# Digital.net
KiCad netlist of a schematic drawn in Altium Designer
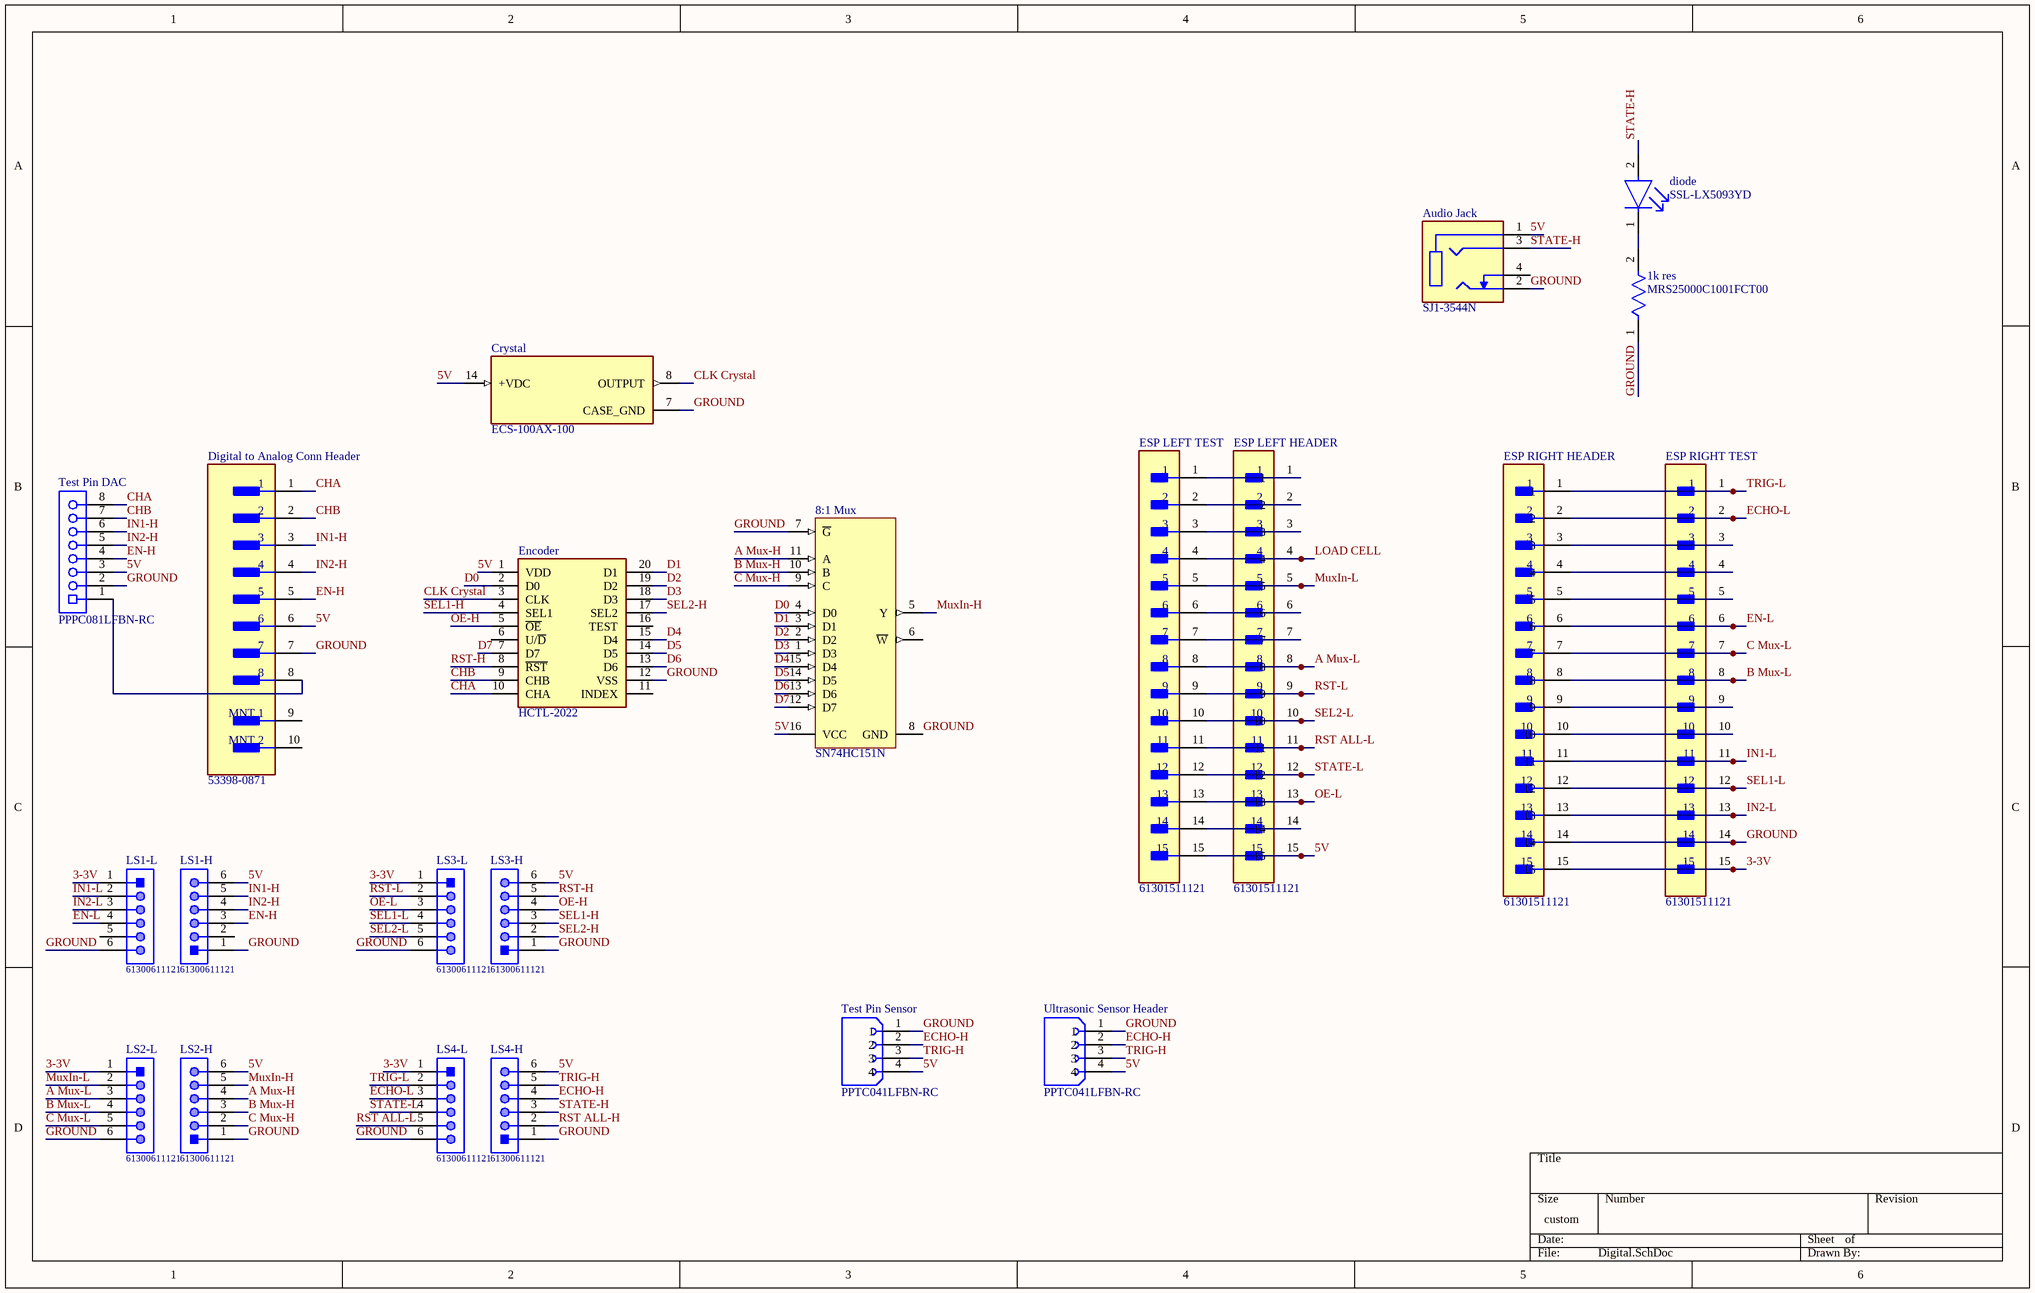
[diagram p0: Digital.SchDoc]

(export (version "E")
  (design (tool "Eeschema 10.0.6"))
  (components
    (comp (ref "1k res")
      (value "MRS25000C1001FCT00")
      (footprint "FP-MRS25-MFG")
      (description "RES 1K OHM 0.6W 1% AXIAL")
      (fields (field (name "TOLERANCE") "1%"))
      (libsource (lib "Altium Content Vault") (part "1029c3af85768c4190bb7ad29bc67b5"))
    )
    (comp (ref "8:1 Mux")
      (value "SN74HC151N")
      (footprint "N0016A")
      (description "8-Line To 1-Line Data Selectors/Multiplexers, N0016A, TUBE")
      (fields
        (field (name "GENERIC PART NUMBER") "SN74HC151")
        (field (name "MANUFACTURER") "Texas Instruments")
      )
      (libsource (lib "Altium Content Vault") (part "TI-SNX4XXX151-16"))
    )
    (comp (ref "Audio Jack")
      (value "SJ1-3544N")
      (footprint "CUI_SJ1-3544N")
      (description "3.5 mm Right-Angle Stereo Jack, 4 Pin PCB Mount, Non-Threaded")
      (libsource (lib "SJ1-3544N") (part "SJ1-3544N"))
    )
    (comp (ref "Crystal")
      (value "ECS-100AX-100")
      (footprint "OSC_ECS-100AX-100")
      (description "Oscillator  14-DIP, 4 Leads (Full Size, Metal Can)")
      (libsource (lib "ECS-100AX-100") (part "ECS-100AX-100"))
    )
    (comp (ref "Digital to Analog Conn Header")
      (value "53398-0871")
      (footprint "FP-53398-0871-MFG")
      (description "CONN HEADER SMD 8POS 1.25MM")
      (fields
        (field (name "MANUFACTURER") "Molex")
        (field (name "OCTOPART") "https://octopart.com/53398-0871-molex-655298")
      )
      (libsource (lib "Altium Content Vault") (part "98b5586d6b3804e276fbd0410cd4945"))
    )
    (comp (ref "diode")
      (value "SSL-LX5093YD")
      (footprint "FP-SSL-LX5093YD-MFG")
      (description "LED YELLOW DIFFUSED T-1 3/4 T/H")
      (libsource (lib "Altium Content Vault") (part "8706943c75ba83719d021d2fdc84c58"))
    )
    (comp (ref "Encoder")
      (value "HCTL-2022")
      (footprint "DIP762W56P254L2591H330Q20N")
      (description "HCTL-2022 quadrature decoder/counter ic Avago Technologies HCTL-2022 Decoder, 20-Pin PDIP")
      (fields (field (name "MOUSER PART NUMBER") "630-HCTL-2022"))
      (libsource (lib "HCTL-2022") (part "HCTL-2022"))
    )
    (comp (ref "ESP LEFT HEADER")
      (value "61301511121")
      (footprint "FP-61301511121-MFG")
      (description "CONN HEADER VERT 15POS 2.54MM")
      (libsource (lib "") (part "9e54aee09c46527fb07af492d4d8164_1"))
    )
    (comp (ref "ESP LEFT TEST")
      (value "61301511121")
      (footprint "FP-61301511121-MFG")
      (description "CONN HEADER VERT 15POS 2.54MM")
      (libsource (lib "Altium Content Vault") (part "9e54aee09c46527fb07af492d4d8164"))
    )
    (comp (ref "ESP RIGHT HEADER")
      (value "61301511121")
      (footprint "FP-61301511121-MFG")
      (description "CONN HEADER VERT 15POS 2.54MM")
      (libsource (lib "") (part "9e54aee09c46527fb07af492d4d8164_1"))
    )
    (comp (ref "ESP RIGHT TEST")
      (value "61301511121")
      (footprint "FP-61301511121-MFG")
      (description "CONN HEADER VERT 15POS 2.54MM")
      (libsource (lib "Altium Content Vault") (part "9e54aee09c46527fb07af492d4d8164"))
    )
    (comp (ref "LS1-H")
      (value "61300611121")
      (footprint "61300611121")
      (description "THT Vertical Pin Header WR-PHD, Pitch 2.54 mm, Single Row, 6 pins")
      (fields (field (name "MANUFACTURER") "Wurth Elektronik") (field (name "PUBLISHER") "WurthElektronik"))
      (libsource (lib "") (part "WE-CN-1P-M-R6_1"))
    )
    (comp (ref "LS1-L")
      (value "61300611121")
      (footprint "61300611121")
      (description "THT Vertical Pin Header WR-PHD, Pitch 2.54 mm, Single Row, 6 pins")
      (fields (field (name "MANUFACTURER") "Wurth Elektronik") (field (name "PUBLISHER") "WurthElektronik"))
      (libsource (lib "Altium Content Vault") (part "WE-CN-1P-M-R6"))
    )
    (comp (ref "LS2-H")
      (value "61300611121")
      (footprint "61300611121")
      (description "THT Vertical Pin Header WR-PHD, Pitch 2.54 mm, Single Row, 6 pins")
      (fields (field (name "MANUFACTURER") "Wurth Elektronik") (field (name "PUBLISHER") "WurthElektronik"))
      (libsource (lib "") (part "WE-CN-1P-M-R6_1"))
    )
    (comp (ref "LS2-L")
      (value "61300611121")
      (footprint "61300611121")
      (description "THT Vertical Pin Header WR-PHD, Pitch 2.54 mm, Single Row, 6 pins")
      (fields (field (name "MANUFACTURER") "Wurth Elektronik") (field (name "PUBLISHER") "WurthElektronik"))
      (libsource (lib "Altium Content Vault") (part "WE-CN-1P-M-R6"))
    )
    (comp (ref "LS3-H")
      (value "61300611121")
      (footprint "61300611121")
      (description "THT Vertical Pin Header WR-PHD, Pitch 2.54 mm, Single Row, 6 pins")
      (fields (field (name "MANUFACTURER") "Wurth Elektronik") (field (name "PUBLISHER") "WurthElektronik"))
      (libsource (lib "") (part "WE-CN-1P-M-R6_1"))
    )
    (comp (ref "LS3-L")
      (value "61300611121")
      (footprint "61300611121")
      (description "THT Vertical Pin Header WR-PHD, Pitch 2.54 mm, Single Row, 6 pins")
      (fields (field (name "MANUFACTURER") "Wurth Elektronik") (field (name "PUBLISHER") "WurthElektronik"))
      (libsource (lib "Altium Content Vault") (part "WE-CN-1P-M-R6"))
    )
    (comp (ref "LS4-H")
      (value "61300611121")
      (footprint "61300611121")
      (description "THT Vertical Pin Header WR-PHD, Pitch 2.54 mm, Single Row, 6 pins")
      (fields (field (name "MANUFACTURER") "Wurth Elektronik") (field (name "PUBLISHER") "WurthElektronik"))
      (libsource (lib "") (part "WE-CN-1P-M-R6_1"))
    )
    (comp (ref "LS4-L")
      (value "61300611121")
      (footprint "61300611121")
      (description "THT Vertical Pin Header WR-PHD, Pitch 2.54 mm, Single Row, 6 pins")
      (fields (field (name "MANUFACTURER") "Wurth Elektronik") (field (name "PUBLISHER") "WurthElektronik"))
      (libsource (lib "Altium Content Vault") (part "WE-CN-1P-M-R6"))
    )
    (comp (ref "Test Pin DAC")
      (value "PPPC081LFBN-RC")
      (footprint "SLIN-PPPC081LFBN-RC_V")
      (libsource (lib "Altium Content Vault") (part "CN-1P-F-R8"))
    )
    (comp (ref "Test Pin Sensor")
      (value "PPTC041LFBN-RC")
      (footprint "SULLINS_PPTC041LFBN-RC")
      (description "4 Position Header Connector 0.100 (2.54mm) Through Hole Tin")
      (fields (field (name "MF") "Sullins Connector") (field (name "DIGI-KEY_PART_NUMBER") "S7002-ND"))
      (libsource (lib "PPTC041LFBN-RC") (part "PPTC041LFBN-RC"))
    )
    (comp (ref "Ultrasonic Sensor Header")
      (value "PPTC041LFBN-RC")
      (footprint "SULLINS_PPTC041LFBN-RC")
      (description "4 Position Header Connector 0.100 (2.54mm) Through Hole Tin")
      (fields (field (name "MF") "Sullins Connector") (field (name "DIGI-KEY_PART_NUMBER") "S7002-ND"))
      (libsource (lib "PPTC041LFBN-RC") (part "PPTC041LFBN-RC"))
    )
  )
  (nets
    (net (code "1") (name "/3-3V") (class "Default")
      (node (ref "ESP RIGHT HEADER") (pin "15") (pinfunction "15_15") (pintype "passive"))
      (node (ref "ESP RIGHT TEST") (pin "15") (pinfunction "15_15") (pintype "passive"))
      (node (ref "LS1-L") (pin "1") (pinfunction "1_1") (pintype "passive"))
      (node (ref "LS2-L") (pin "1") (pinfunction "1_1") (pintype "passive"))
      (node (ref "LS3-L") (pin "1") (pinfunction "1_1") (pintype "passive"))
      (node (ref "LS4-L") (pin "1") (pinfunction "1_1") (pintype "passive"))
    )
    (net (code "2") (name "/5V") (class "Default")
      (node (ref "8:1 Mux") (pin "16") (pinfunction "VCC_16") (pintype "power_in"))
      (node (ref "Audio Jack") (pin "1") (pinfunction "1_1") (pintype "passive"))
      (node (ref "Crystal") (pin "14") (pinfunction "+VDC_14") (pintype "input"))
      (node (ref "Digital to Analog Conn Header") (pin "6") (pinfunction "6_6") (pintype "passive"))
      (node (ref "ESP LEFT HEADER") (pin "15") (pinfunction "15_15") (pintype "passive"))
      (node (ref "ESP LEFT TEST") (pin "15") (pinfunction "15_15") (pintype "passive"))
      (node (ref "Encoder") (pin "1") (pinfunction "VDD_1") (pintype "power_in"))
      (node (ref "LS1-H") (pin "6") (pinfunction "6_6") (pintype "passive"))
      (node (ref "LS2-H") (pin "6") (pinfunction "6_6") (pintype "passive"))
      (node (ref "LS3-H") (pin "6") (pinfunction "6_6") (pintype "passive"))
      (node (ref "LS4-H") (pin "6") (pinfunction "6_6") (pintype "passive"))
      (node (ref "Test Pin DAC") (pin "3") (pinfunction "3_3") (pintype "passive"))
      (node (ref "Test Pin Sensor") (pin "4") (pinfunction "4_4") (pintype "passive"))
      (node (ref "Ultrasonic Sensor Header") (pin "4") (pinfunction "4_4") (pintype "passive"))
    )
    (net (code "3") (name "/A Mux-H") (class "Default")
      (node (ref "8:1 Mux") (pin "11") (pinfunction "A_11") (pintype "input"))
      (node (ref "LS2-H") (pin "4") (pinfunction "4_4") (pintype "passive"))
    )
    (net (code "4") (name "/A Mux-L") (class "Default")
      (node (ref "ESP LEFT HEADER") (pin "8") (pinfunction "8_8") (pintype "passive"))
      (node (ref "ESP LEFT TEST") (pin "8") (pinfunction "8_8") (pintype "passive"))
      (node (ref "LS2-L") (pin "3") (pinfunction "3_3") (pintype "passive"))
    )
    (net (code "5") (name "/B Mux-H") (class "Default")
      (node (ref "8:1 Mux") (pin "10") (pinfunction "B_10") (pintype "input"))
      (node (ref "LS2-H") (pin "3") (pinfunction "3_3") (pintype "passive"))
    )
    (net (code "6") (name "/B Mux-L") (class "Default")
      (node (ref "ESP RIGHT HEADER") (pin "8") (pinfunction "8_8") (pintype "passive"))
      (node (ref "ESP RIGHT TEST") (pin "8") (pinfunction "8_8") (pintype "passive"))
      (node (ref "LS2-L") (pin "4") (pinfunction "4_4") (pintype "passive"))
    )
    (net (code "7") (name "/C Mux-H") (class "Default")
      (node (ref "8:1 Mux") (pin "9") (pinfunction "C_9") (pintype "input"))
      (node (ref "LS2-H") (pin "2") (pinfunction "2_2") (pintype "passive"))
    )
    (net (code "8") (name "/C Mux-L") (class "Default")
      (node (ref "ESP RIGHT HEADER") (pin "7") (pinfunction "7_7") (pintype "passive"))
      (node (ref "ESP RIGHT TEST") (pin "7") (pinfunction "7_7") (pintype "passive"))
      (node (ref "LS2-L") (pin "5") (pinfunction "5_5") (pintype "passive"))
    )
    (net (code "9") (name "/CHA") (class "Default")
      (node (ref "Digital to Analog Conn Header") (pin "1") (pinfunction "1_1") (pintype "passive"))
      (node (ref "Encoder") (pin "10") (pinfunction "CHA_10") (pintype "passive"))
      (node (ref "Test Pin DAC") (pin "8") (pinfunction "8_8") (pintype "passive"))
    )
    (net (code "10") (name "/CHB") (class "Default")
      (node (ref "Digital to Analog Conn Header") (pin "2") (pinfunction "2_2") (pintype "passive"))
      (node (ref "Encoder") (pin "9") (pinfunction "CHB_9") (pintype "passive"))
      (node (ref "Test Pin DAC") (pin "7") (pinfunction "7_7") (pintype "passive"))
    )
    (net (code "11") (name "/CLK Crystal") (class "Default")
      (node (ref "Crystal") (pin "8") (pinfunction "OUTPUT_8") (pintype "output"))
      (node (ref "Encoder") (pin "3") (pinfunction "CLK_3") (pintype "passive"))
    )
    (net (code "12") (name "/D0") (class "Default")
      (node (ref "8:1 Mux") (pin "4") (pinfunction "D0_4") (pintype "input"))
      (node (ref "Encoder") (pin "2") (pinfunction "D0_2") (pintype "passive"))
    )
    (net (code "13") (name "/D1") (class "Default")
      (node (ref "8:1 Mux") (pin "3") (pinfunction "D1_3") (pintype "input"))
      (node (ref "Encoder") (pin "20") (pinfunction "D1_20") (pintype "passive"))
    )
    (net (code "14") (name "/D2") (class "Default")
      (node (ref "8:1 Mux") (pin "2") (pinfunction "D2_2") (pintype "input"))
      (node (ref "Encoder") (pin "19") (pinfunction "D2_19") (pintype "passive"))
    )
    (net (code "15") (name "/D3") (class "Default")
      (node (ref "8:1 Mux") (pin "1") (pinfunction "D3_1") (pintype "input"))
      (node (ref "Encoder") (pin "18") (pinfunction "D3_18") (pintype "passive"))
    )
    (net (code "16") (name "/D4") (class "Default")
      (node (ref "8:1 Mux") (pin "15") (pinfunction "D4_15") (pintype "input"))
      (node (ref "Encoder") (pin "15") (pinfunction "D4_15") (pintype "passive"))
    )
    (net (code "17") (name "/D5") (class "Default")
      (node (ref "8:1 Mux") (pin "14") (pinfunction "D5_14") (pintype "input"))
      (node (ref "Encoder") (pin "14") (pinfunction "D5_14") (pintype "passive"))
    )
    (net (code "18") (name "/D6") (class "Default")
      (node (ref "8:1 Mux") (pin "13") (pinfunction "D6_13") (pintype "input"))
      (node (ref "Encoder") (pin "13") (pinfunction "D6_13") (pintype "passive"))
    )
    (net (code "19") (name "/D7") (class "Default")
      (node (ref "8:1 Mux") (pin "12") (pinfunction "D7_12") (pintype "input"))
      (node (ref "Encoder") (pin "7") (pinfunction "D7_7") (pintype "passive"))
    )
    (net (code "20") (name "/ECHO-H") (class "Default")
      (node (ref "LS4-H") (pin "4") (pinfunction "4_4") (pintype "passive"))
      (node (ref "Test Pin Sensor") (pin "2") (pinfunction "2_2") (pintype "passive"))
      (node (ref "Ultrasonic Sensor Header") (pin "2") (pinfunction "2_2") (pintype "passive"))
    )
    (net (code "21") (name "/ECHO-L") (class "Default")
      (node (ref "ESP RIGHT HEADER") (pin "2") (pinfunction "2_2") (pintype "passive"))
      (node (ref "ESP RIGHT TEST") (pin "2") (pinfunction "2_2") (pintype "passive"))
      (node (ref "LS4-L") (pin "3") (pinfunction "3_3") (pintype "passive"))
    )
    (net (code "22") (name "/EN-H") (class "Default")
      (node (ref "Digital to Analog Conn Header") (pin "5") (pinfunction "5_5") (pintype "passive"))
      (node (ref "LS1-H") (pin "3") (pinfunction "3_3") (pintype "passive"))
      (node (ref "Test Pin DAC") (pin "4") (pinfunction "4_4") (pintype "passive"))
    )
    (net (code "23") (name "/EN-L") (class "Default")
      (node (ref "ESP RIGHT HEADER") (pin "6") (pinfunction "6_6") (pintype "passive"))
      (node (ref "ESP RIGHT TEST") (pin "6") (pinfunction "6_6") (pintype "passive"))
      (node (ref "LS1-L") (pin "4") (pinfunction "4_4") (pintype "passive"))
    )
    (net (code "24") (name "/GROUND") (class "Default")
      (node (ref "1k res") (pin "1") (pinfunction "1_1") (pintype "passive"))
      (node (ref "8:1 Mux") (pin "7") (pinfunction "~{G}_7") (pintype "input"))
      (node (ref "8:1 Mux") (pin "8") (pinfunction "GND_8") (pintype "power_in"))
      (node (ref "Audio Jack") (pin "2") (pinfunction "2_2") (pintype "passive"))
      (node (ref "Crystal") (pin "7") (pinfunction "CASE_GND_7") (pintype "power_in"))
      (node (ref "Digital to Analog Conn Header") (pin "7") (pinfunction "7_7") (pintype "passive"))
      (node (ref "ESP RIGHT HEADER") (pin "14") (pinfunction "14_14") (pintype "passive"))
      (node (ref "ESP RIGHT TEST") (pin "14") (pinfunction "14_14") (pintype "passive"))
      (node (ref "Encoder") (pin "12") (pinfunction "VSS_12") (pintype "passive"))
      (node (ref "LS1-H") (pin "1") (pinfunction "1_1") (pintype "passive"))
      (node (ref "LS1-L") (pin "6") (pinfunction "6_6") (pintype "passive"))
      (node (ref "LS2-H") (pin "1") (pinfunction "1_1") (pintype "passive"))
      (node (ref "LS2-L") (pin "6") (pinfunction "6_6") (pintype "passive"))
      (node (ref "LS3-H") (pin "1") (pinfunction "1_1") (pintype "passive"))
      (node (ref "LS3-L") (pin "6") (pinfunction "6_6") (pintype "passive"))
      (node (ref "LS4-H") (pin "1") (pinfunction "1_1") (pintype "passive"))
      (node (ref "LS4-L") (pin "6") (pinfunction "6_6") (pintype "passive"))
      (node (ref "Test Pin DAC") (pin "2") (pinfunction "2_2") (pintype "passive"))
      (node (ref "Test Pin Sensor") (pin "1") (pinfunction "1_1") (pintype "passive"))
      (node (ref "Ultrasonic Sensor Header") (pin "1") (pinfunction "1_1") (pintype "passive"))
    )
    (net (code "25") (name "/IN1-H") (class "Default")
      (node (ref "Digital to Analog Conn Header") (pin "3") (pinfunction "3_3") (pintype "passive"))
      (node (ref "LS1-H") (pin "5") (pinfunction "5_5") (pintype "passive"))
      (node (ref "Test Pin DAC") (pin "6") (pinfunction "6_6") (pintype "passive"))
    )
    (net (code "26") (name "/IN1-L") (class "Default")
      (node (ref "ESP RIGHT HEADER") (pin "11") (pinfunction "11_11") (pintype "passive"))
      (node (ref "ESP RIGHT TEST") (pin "11") (pinfunction "11_11") (pintype "passive"))
      (node (ref "LS1-L") (pin "2") (pinfunction "2_2") (pintype "passive"))
    )
    (net (code "27") (name "/IN2-H") (class "Default")
      (node (ref "Digital to Analog Conn Header") (pin "4") (pinfunction "4_4") (pintype "passive"))
      (node (ref "LS1-H") (pin "4") (pinfunction "4_4") (pintype "passive"))
      (node (ref "Test Pin DAC") (pin "5") (pinfunction "5_5") (pintype "passive"))
    )
    (net (code "28") (name "/IN2-L") (class "Default")
      (node (ref "ESP RIGHT HEADER") (pin "13") (pinfunction "13_13") (pintype "passive"))
      (node (ref "ESP RIGHT TEST") (pin "13") (pinfunction "13_13") (pintype "passive"))
      (node (ref "LS1-L") (pin "3") (pinfunction "3_3") (pintype "passive"))
    )
    (net (code "29") (name "/LOAD CELL") (class "Default")
      (node (ref "ESP LEFT HEADER") (pin "4") (pinfunction "4_4") (pintype "passive"))
      (node (ref "ESP LEFT TEST") (pin "4") (pinfunction "4_4") (pintype "passive"))
    )
    (net (code "30") (name "/MuxIn-H") (class "Default")
      (node (ref "8:1 Mux") (pin "5") (pinfunction "Y_5") (pintype "output"))
      (node (ref "LS2-H") (pin "5") (pinfunction "5_5") (pintype "passive"))
    )
    (net (code "31") (name "/MuxIn-L") (class "Default")
      (node (ref "ESP LEFT HEADER") (pin "5") (pinfunction "5_5") (pintype "passive"))
      (node (ref "ESP LEFT TEST") (pin "5") (pinfunction "5_5") (pintype "passive"))
      (node (ref "LS2-L") (pin "2") (pinfunction "2_2") (pintype "passive"))
    )
    (net (code "32") (name "/OE-H") (class "Default")
      (node (ref "Encoder") (pin "5") (pinfunction "~{OE}_5") (pintype "passive"))
      (node (ref "LS3-H") (pin "4") (pinfunction "4_4") (pintype "passive"))
    )
    (net (code "33") (name "/OE-L") (class "Default")
      (node (ref "ESP LEFT HEADER") (pin "13") (pinfunction "13_13") (pintype "passive"))
      (node (ref "ESP LEFT TEST") (pin "13") (pinfunction "13_13") (pintype "passive"))
      (node (ref "LS3-L") (pin "3") (pinfunction "3_3") (pintype "passive"))
    )
    (net (code "34") (name "/RST ALL-H") (class "Default")
      (node (ref "LS4-H") (pin "2") (pinfunction "2_2") (pintype "passive"))
    )
    (net (code "35") (name "/RST ALL-L") (class "Default")
      (node (ref "ESP LEFT HEADER") (pin "11") (pinfunction "11_11") (pintype "passive"))
      (node (ref "ESP LEFT TEST") (pin "11") (pinfunction "11_11") (pintype "passive"))
      (node (ref "LS4-L") (pin "5") (pinfunction "5_5") (pintype "passive"))
    )
    (net (code "36") (name "/RST-H") (class "Default")
      (node (ref "Encoder") (pin "8") (pinfunction "~{RST}_8") (pintype "passive"))
      (node (ref "LS3-H") (pin "5") (pinfunction "5_5") (pintype "passive"))
    )
    (net (code "37") (name "/RST-L") (class "Default")
      (node (ref "ESP LEFT HEADER") (pin "9") (pinfunction "9_9") (pintype "passive"))
      (node (ref "ESP LEFT TEST") (pin "9") (pinfunction "9_9") (pintype "passive"))
      (node (ref "LS3-L") (pin "2") (pinfunction "2_2") (pintype "passive"))
    )
    (net (code "38") (name "/SEL1-H") (class "Default")
      (node (ref "Encoder") (pin "4") (pinfunction "SEL1_4") (pintype "passive"))
      (node (ref "LS3-H") (pin "3") (pinfunction "3_3") (pintype "passive"))
    )
    (net (code "39") (name "/SEL1-L") (class "Default")
      (node (ref "ESP RIGHT HEADER") (pin "12") (pinfunction "12_12") (pintype "passive"))
      (node (ref "ESP RIGHT TEST") (pin "12") (pinfunction "12_12") (pintype "passive"))
      (node (ref "LS3-L") (pin "4") (pinfunction "4_4") (pintype "passive"))
    )
    (net (code "40") (name "/SEL2-H") (class "Default")
      (node (ref "Encoder") (pin "17") (pinfunction "SEL2_17") (pintype "passive"))
      (node (ref "LS3-H") (pin "2") (pinfunction "2_2") (pintype "passive"))
    )
    (net (code "41") (name "/SEL2-L") (class "Default")
      (node (ref "ESP LEFT HEADER") (pin "10") (pinfunction "10_10") (pintype "passive"))
      (node (ref "ESP LEFT TEST") (pin "10") (pinfunction "10_10") (pintype "passive"))
      (node (ref "LS3-L") (pin "5") (pinfunction "5_5") (pintype "passive"))
    )
    (net (code "42") (name "/STATE-H") (class "Default")
      (node (ref "Audio Jack") (pin "3") (pinfunction "3_3") (pintype "passive"))
      (node (ref "LS4-H") (pin "3") (pinfunction "3_3") (pintype "passive"))
      (node (ref "diode") (pin "2") (pinfunction "A_2") (pintype "passive"))
    )
    (net (code "43") (name "/STATE-L") (class "Default")
      (node (ref "ESP LEFT HEADER") (pin "12") (pinfunction "12_12") (pintype "passive"))
      (node (ref "ESP LEFT TEST") (pin "12") (pinfunction "12_12") (pintype "passive"))
      (node (ref "LS4-L") (pin "4") (pinfunction "4_4") (pintype "passive"))
    )
    (net (code "44") (name "/TRIG-H") (class "Default")
      (node (ref "LS4-H") (pin "5") (pinfunction "5_5") (pintype "passive"))
      (node (ref "Test Pin Sensor") (pin "3") (pinfunction "3_3") (pintype "passive"))
      (node (ref "Ultrasonic Sensor Header") (pin "3") (pinfunction "3_3") (pintype "passive"))
    )
    (net (code "45") (name "/TRIG-L") (class "Default")
      (node (ref "ESP RIGHT HEADER") (pin "1") (pinfunction "1_1") (pintype "passive"))
      (node (ref "ESP RIGHT TEST") (pin "1") (pinfunction "1_1") (pintype "passive"))
      (node (ref "LS4-L") (pin "2") (pinfunction "2_2") (pintype "passive"))
    )
    (net (code "46") (name "Net-(Digital to Analog Conn Header-Pad8)") (class "Default")
      (node (ref "Digital to Analog Conn Header") (pin "8") (pinfunction "8_8") (pintype "passive"))
      (node (ref "Test Pin DAC") (pin "1") (pinfunction "1_1") (pintype "passive"))
    )
    (net (code "47") (name "Net-(ESP LEFT HEADER-Pad1)") (class "Default")
      (node (ref "ESP LEFT HEADER") (pin "1") (pinfunction "1_1") (pintype "passive"))
      (node (ref "ESP LEFT TEST") (pin "1") (pinfunction "1_1") (pintype "passive"))
    )
    (net (code "48") (name "Net-(ESP LEFT HEADER-Pad2)") (class "Default")
      (node (ref "ESP LEFT HEADER") (pin "2") (pinfunction "2_2") (pintype "passive"))
      (node (ref "ESP LEFT TEST") (pin "2") (pinfunction "2_2") (pintype "passive"))
    )
    (net (code "49") (name "Net-(ESP LEFT HEADER-Pad3)") (class "Default")
      (node (ref "ESP LEFT HEADER") (pin "3") (pinfunction "3_3") (pintype "passive"))
      (node (ref "ESP LEFT TEST") (pin "3") (pinfunction "3_3") (pintype "passive"))
    )
    (net (code "50") (name "Net-(ESP LEFT HEADER-Pad6)") (class "Default")
      (node (ref "ESP LEFT HEADER") (pin "6") (pinfunction "6_6") (pintype "passive"))
      (node (ref "ESP LEFT TEST") (pin "6") (pinfunction "6_6") (pintype "passive"))
    )
    (net (code "51") (name "Net-(ESP LEFT HEADER-Pad7)") (class "Default")
      (node (ref "ESP LEFT HEADER") (pin "7") (pinfunction "7_7") (pintype "passive"))
      (node (ref "ESP LEFT TEST") (pin "7") (pinfunction "7_7") (pintype "passive"))
    )
    (net (code "52") (name "Net-(ESP LEFT HEADER-Pad14)") (class "Default")
      (node (ref "ESP LEFT HEADER") (pin "14") (pinfunction "14_14") (pintype "passive"))
      (node (ref "ESP LEFT TEST") (pin "14") (pinfunction "14_14") (pintype "passive"))
    )
    (net (code "53") (name "Net-(ESP RIGHT HEADER-Pad3)") (class "Default")
      (node (ref "ESP RIGHT HEADER") (pin "3") (pinfunction "3_3") (pintype "passive"))
      (node (ref "ESP RIGHT TEST") (pin "3") (pinfunction "3_3") (pintype "passive"))
    )
    (net (code "54") (name "Net-(ESP RIGHT HEADER-Pad4)") (class "Default")
      (node (ref "ESP RIGHT HEADER") (pin "4") (pinfunction "4_4") (pintype "passive"))
      (node (ref "ESP RIGHT TEST") (pin "4") (pinfunction "4_4") (pintype "passive"))
    )
    (net (code "55") (name "Net-(ESP RIGHT HEADER-Pad5)") (class "Default")
      (node (ref "ESP RIGHT HEADER") (pin "5") (pinfunction "5_5") (pintype "passive"))
      (node (ref "ESP RIGHT TEST") (pin "5") (pinfunction "5_5") (pintype "passive"))
    )
    (net (code "56") (name "Net-(ESP RIGHT HEADER-Pad9)") (class "Default")
      (node (ref "ESP RIGHT HEADER") (pin "9") (pinfunction "9_9") (pintype "passive"))
      (node (ref "ESP RIGHT TEST") (pin "9") (pinfunction "9_9") (pintype "passive"))
    )
    (net (code "57") (name "Net-(ESP RIGHT HEADER-Pad10)") (class "Default")
      (node (ref "ESP RIGHT HEADER") (pin "10") (pinfunction "10_10") (pintype "passive"))
      (node (ref "ESP RIGHT TEST") (pin "10") (pinfunction "10_10") (pintype "passive"))
    )
    (net (code "58") (name "Net-(diode-C)") (class "Default")
      (node (ref "1k res") (pin "2") (pinfunction "2_2") (pintype "passive"))
      (node (ref "diode") (pin "1") (pinfunction "C_1") (pintype "passive"))
    )
    (net (code "59") (name "unconnected-(8:1 Mux-~{W}-Pad6)") (class "Default")
      (node (ref "8:1 Mux") (pin "6") (pinfunction "~{W}_6") (pintype "output"))
    )
    (net (code "60") (name "unconnected-(Audio Jack-Pad4)") (class "Default")
      (node (ref "Audio Jack") (pin "4") (pinfunction "4_4") (pintype "passive"))
    )
    (net (code "61") (name "unconnected-(Digital to Analog Conn Header-MNT_1-Pad9)") (class "Default")
      (node (ref "Digital to Analog Conn Header") (pin "9") (pinfunction "MNT_1_9") (pintype "passive"))
    )
    (net (code "62") (name "unconnected-(Digital to Analog Conn Header-MNT_2-Pad10)") (class "Default")
      (node (ref "Digital to Analog Conn Header") (pin "10") (pinfunction "MNT_2_10") (pintype "passive"))
    )
    (net (code "63") (name "unconnected-(Encoder-INDEX-Pad11)") (class "Default")
      (node (ref "Encoder") (pin "11") (pinfunction "INDEX_11") (pintype "passive"))
    )
    (net (code "64") (name "unconnected-(Encoder-TEST-Pad16)") (class "Default")
      (node (ref "Encoder") (pin "16") (pinfunction "TEST_16") (pintype "passive"))
    )
    (net (code "65") (name "unconnected-(Encoder-U{slash}~{D}-Pad6)") (class "Default")
      (node (ref "Encoder") (pin "6") (pinfunction "U/~{D}_6") (pintype "passive"))
    )
    (net (code "66") (name "unconnected-(LS1-H-Pad2)") (class "Default")
      (node (ref "LS1-H") (pin "2") (pinfunction "2_2") (pintype "passive"))
    )
    (net (code "67") (name "unconnected-(LS1-L-Pad5)") (class "Default")
      (node (ref "LS1-L") (pin "5") (pinfunction "5_5") (pintype "passive"))
    )
  )
)
